# KIS-3R33.net
KiCad netlist of a schematic drawn in EAGLE
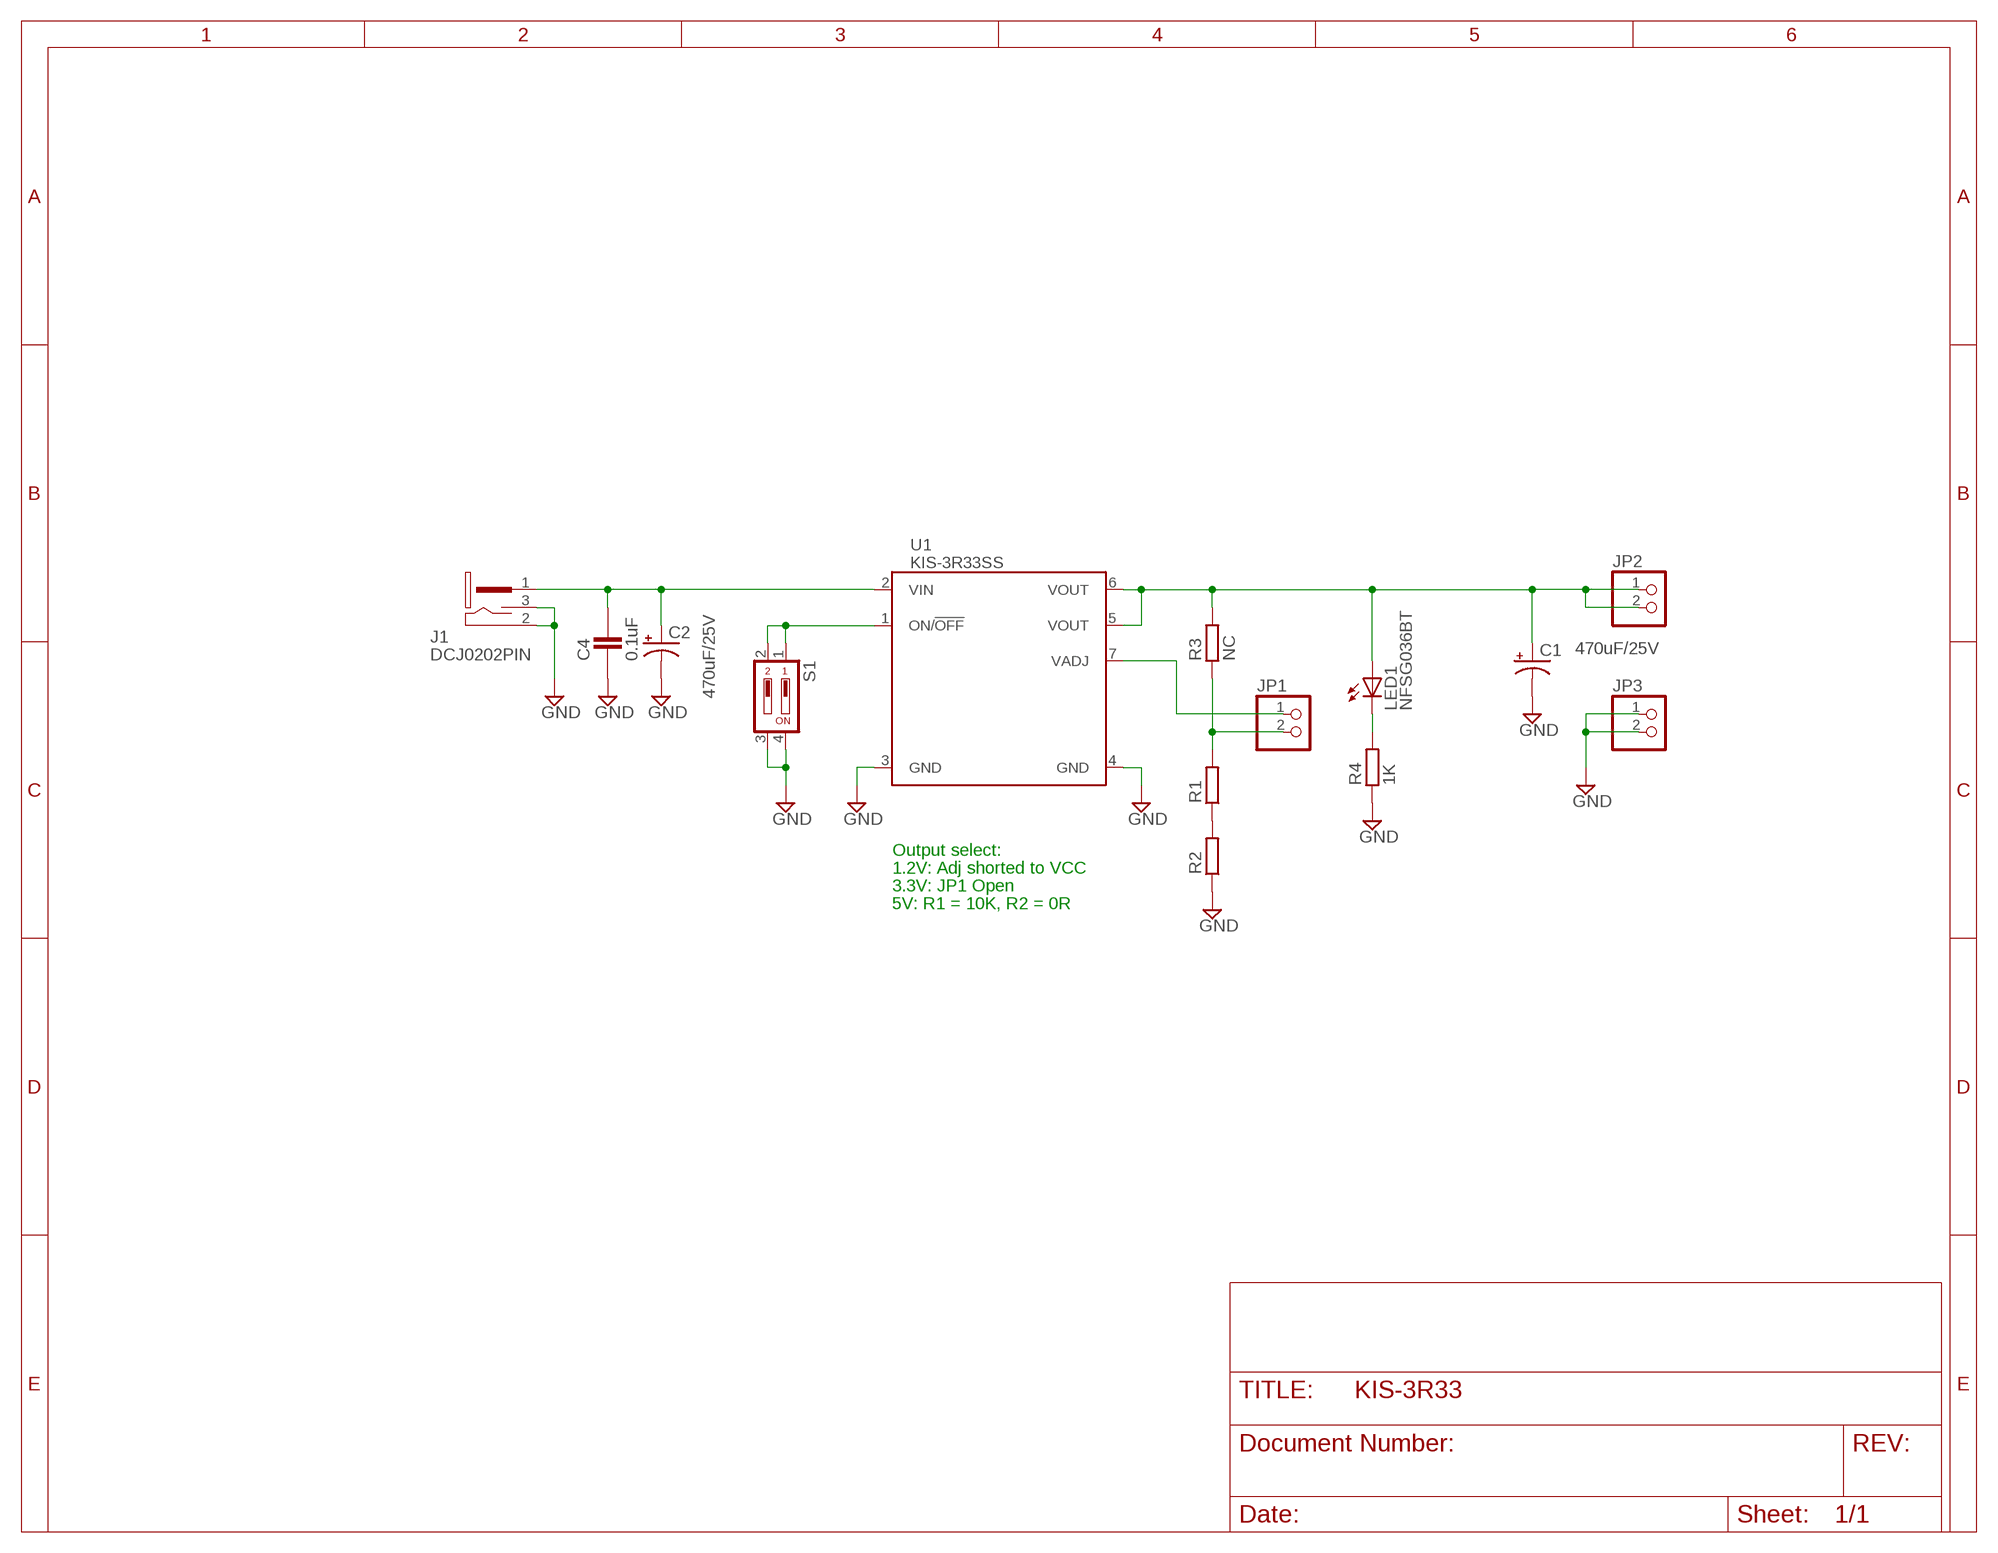
[diagram p0: schematic, sheet 1]

(export (version "E")
  (design (tool "Eeschema 10.0.6"))
  (components
    (comp (ref "C1")
      (value "470uF/25V")
      (footprint "eagle-import:PANASONIC_G")
      (libsource (lib "eagle-import") (part "CAP_POLG"))
    )
    (comp (ref "C2")
      (value "470uF/25V")
      (footprint "eagle-import:PANASONIC_G")
      (libsource (lib "eagle-import") (part "CAP_POLG"))
    )
    (comp (ref "C4")
      (value "0.1uF")
      (footprint "eagle-import:CAP2012X70N")
      (libsource (lib "eagle-import") (part "CAPACITOR_0805N"))
    )
    (comp (ref "J1")
      (value "DCJ0202PIN")
      (footprint "eagle-import:PJ-102A")
      (libsource (lib "eagle-import") (part "DCJ0202PIN"))
    )
    (comp (ref "JP1")
      (value "PINHD-1X2_2.54-SMD")
      (footprint "eagle-import:1X02SMD")
      (libsource (lib "eagle-import") (part "PINHD-1X2_2.54-SMD"))
    )
    (comp (ref "JP2")
      (value "PINHD-1X2_2.54")
      (footprint "eagle-import:1X02")
      (libsource (lib "eagle-import") (part "PINHD-1X2_2.54"))
    )
    (comp (ref "JP3")
      (value "PINHD-1X2_2.54")
      (footprint "eagle-import:1X02")
      (libsource (lib "eagle-import") (part "PINHD-1X2_2.54"))
    )
    (comp (ref "LED1")
      (value "NFSG036BT")
      (footprint "eagle-import:NFSG036BT")
      (libsource (lib "eagle-import") (part "NFSG036BT"))
    )
    (comp (ref "R1")
      (value "RESISTOR_1206")
      (footprint "eagle-import:RESC3115X70N")
      (libsource (lib "eagle-import") (part "RESISTOR_1206"))
    )
    (comp (ref "R2")
      (value "RESISTOR_1206")
      (footprint "eagle-import:RESC3115X70N")
      (libsource (lib "eagle-import") (part "RESISTOR_1206"))
    )
    (comp (ref "R3")
      (value "NC")
      (footprint "eagle-import:RESC3115X70N")
      (libsource (lib "eagle-import") (part "RESISTOR_1206"))
    )
    (comp (ref "R4")
      (value "1K")
      (footprint "eagle-import:RESC1608X55N")
      (libsource (lib "eagle-import") (part "RESISTOR_0603"))
    )
    (comp (ref "S1")
      (value "DIP02YL")
      (footprint "eagle-import:DIP02YL")
      (libsource (lib "eagle-import") (part "DIP02YL"))
    )
    (comp (ref "U1")
      (value "KIS-3R33SS")
      (footprint "eagle-import:KIS-3R33S-SMT")
      (libsource (lib "eagle-import") (part "KIS-3R33SS"))
    )
  )
  (nets
    (net (code "1") (name "GND") (class "Default")
      (node (ref "C1") (pin "-") (pinfunction "-_-") (pintype "passive"))
      (node (ref "C2") (pin "-") (pinfunction "-_-") (pintype "passive"))
      (node (ref "C4") (pin "1") (pinfunction "1_1") (pintype "passive"))
      (node (ref "J1") (pin "2") (pinfunction "3_2") (pintype "passive"))
      (node (ref "J1") (pin "3") (pinfunction "2_3") (pintype "passive"))
      (node (ref "JP3") (pin "1") (pinfunction "1_1") (pintype "passive"))
      (node (ref "JP3") (pin "2") (pinfunction "2_2") (pintype "passive"))
      (node (ref "R2") (pin "1") (pinfunction "1_1") (pintype "passive"))
      (node (ref "R4") (pin "1") (pinfunction "1_1") (pintype "passive"))
      (node (ref "S1") (pin "3") (pinfunction "3_3") (pintype "passive"))
      (node (ref "S1") (pin "4") (pinfunction "4_4") (pintype "passive"))
      (node (ref "U1") (pin "3") (pinfunction "GND_3") (pintype "power_in"))
      (node (ref "U1") (pin "4") (pinfunction "GND_4") (pintype "power_in"))
    )
    (net (code "2") (name "Net-(C1-Pad+)") (class "Default")
      (node (ref "C1") (pin "+") (pinfunction "+_+") (pintype "passive"))
      (node (ref "JP2") (pin "1") (pinfunction "1_1") (pintype "passive"))
      (node (ref "JP2") (pin "2") (pinfunction "2_2") (pintype "passive"))
      (node (ref "LED1") (pin "A") (pinfunction "A_A") (pintype "passive"))
      (node (ref "R3") (pin "2") (pinfunction "2_2") (pintype "passive"))
      (node (ref "U1") (pin "5") (pinfunction "VOUT_5") (pintype "power_in"))
      (node (ref "U1") (pin "6") (pinfunction "VOUT_6") (pintype "power_in"))
    )
    (net (code "3") (name "Net-(JP1-Pad2)") (class "Default")
      (node (ref "JP1") (pin "2") (pinfunction "2_2") (pintype "passive"))
      (node (ref "R1") (pin "2") (pinfunction "2_2") (pintype "passive"))
      (node (ref "R3") (pin "1") (pinfunction "1_1") (pintype "passive"))
    )
    (net (code "4") (name "Net-(LED1-PadC)") (class "Default")
      (node (ref "LED1") (pin "C") (pinfunction "C_C") (pintype "passive"))
      (node (ref "R4") (pin "2") (pinfunction "2_2") (pintype "passive"))
    )
    (net (code "5") (name "Net-(R1-Pad1)") (class "Default")
      (node (ref "R1") (pin "1") (pinfunction "1_1") (pintype "passive"))
      (node (ref "R2") (pin "2") (pinfunction "2_2") (pintype "passive"))
    )
    (net (code "6") (name "Net-(U1-ON{slash}~{OFF})") (class "Default")
      (node (ref "S1") (pin "1") (pinfunction "1_1") (pintype "passive"))
      (node (ref "S1") (pin "2") (pinfunction "2_2") (pintype "passive"))
      (node (ref "U1") (pin "1") (pinfunction "ON/~{OFF}_1") (pintype "input"))
    )
    (net (code "7") (name "Net-(U1-VADJ)") (class "Default")
      (node (ref "JP1") (pin "1") (pinfunction "1_1") (pintype "passive"))
      (node (ref "U1") (pin "7") (pinfunction "VADJ_7") (pintype "power_in"))
    )
    (net (code "8") (name "Net-(U1-VIN)") (class "Default")
      (node (ref "C2") (pin "+") (pinfunction "+_+") (pintype "passive"))
      (node (ref "C4") (pin "2") (pinfunction "2_2") (pintype "passive"))
      (node (ref "J1") (pin "1") (pinfunction "1_1") (pintype "passive"))
      (node (ref "U1") (pin "2") (pinfunction "VIN_2") (pintype "power_in"))
    )
  )
)
